# PCB-PWR-DIST.net
KiCad netlist of a schematic drawn in EAGLE
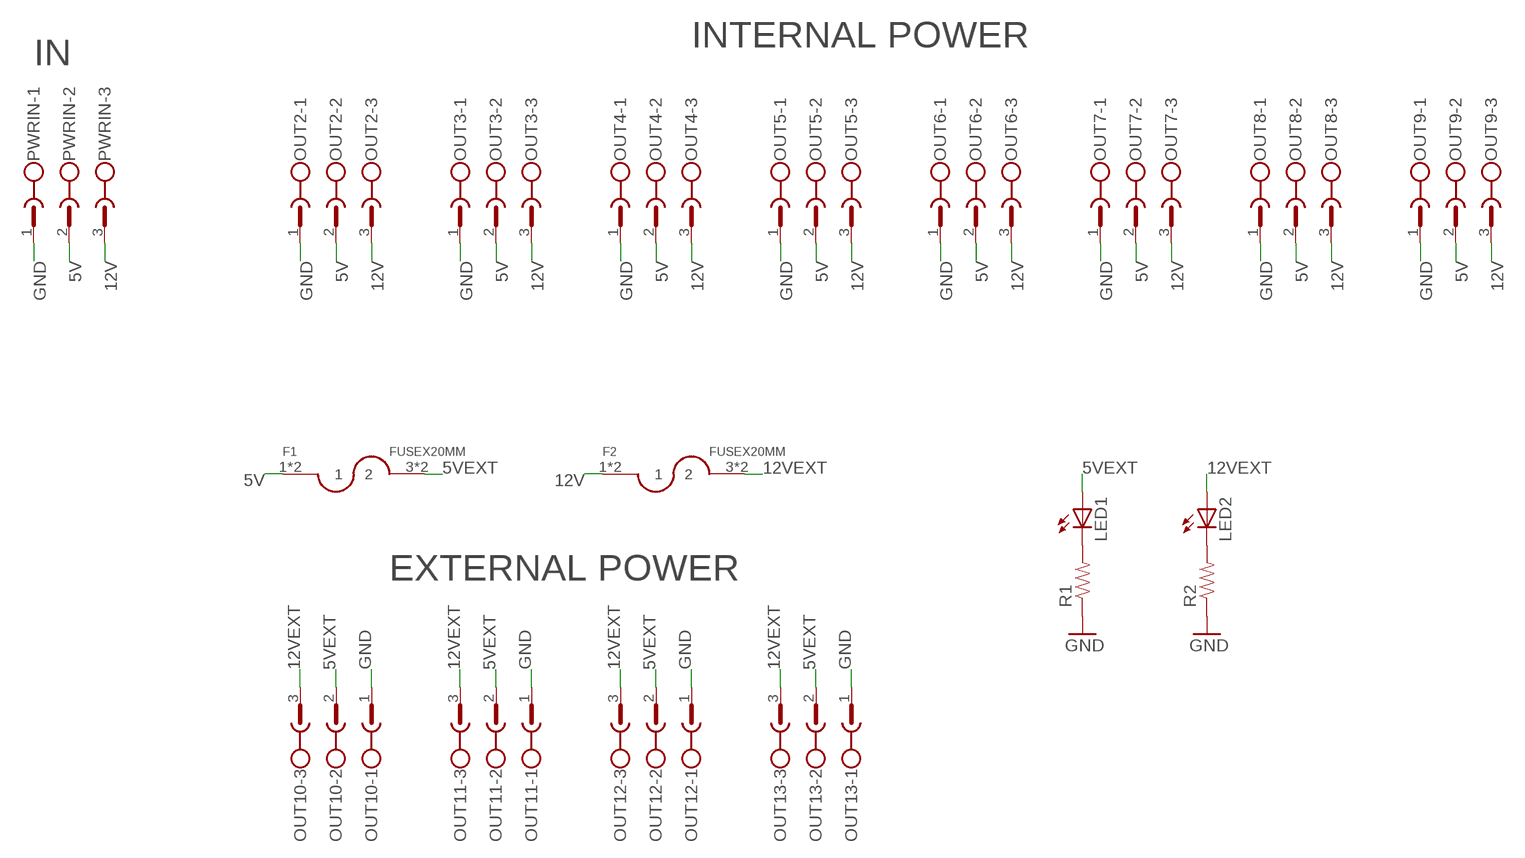
[diagram p0: schematic, sheet 1]

(export (version "E")
  (design (tool "Eeschema 10.0.6"))
  (components
    (comp (ref "F1")
      (value "FUSEX20MM")
      (footprint "eagle-import:FUSE_5MM")
      (libsource (lib "eagle-import") (part "FUSEX20MM"))
    )
    (comp (ref "F2")
      (value "FUSEX20MM")
      (footprint "eagle-import:FUSE_5MM")
      (libsource (lib "eagle-import") (part "FUSEX20MM"))
    )
    (comp (ref "LED1")
      (value "LED3MM")
      (footprint "eagle-import:LED3MM")
      (libsource (lib "eagle-import") (part "LED3MM"))
    )
    (comp (ref "LED2")
      (value "LED3MM")
      (footprint "eagle-import:LED3MM")
      (libsource (lib "eagle-import") (part "LED3MM"))
    )
    (comp (ref "OUT2")
      (value "CON1")
      (footprint "eagle-import:MSTBV3")
      (fields (field (name "MPN") "MSTBV 2,5/3-GF-5.08"))
      (libsource (lib "eagle-import") (part "MSTBV3"))
    )
    (comp (ref "OUT3")
      (value "CON1")
      (footprint "eagle-import:MSTBV3")
      (fields (field (name "MPN") "MSTBV 2,5/3-GF-5.08"))
      (libsource (lib "eagle-import") (part "MSTBV3"))
    )
    (comp (ref "OUT4")
      (value "CON1")
      (footprint "eagle-import:MSTBV3")
      (fields (field (name "MPN") "MSTBV 2,5/3-GF-5.08"))
      (libsource (lib "eagle-import") (part "MSTBV3"))
    )
    (comp (ref "OUT5")
      (value "CON1")
      (footprint "eagle-import:MSTBV3")
      (fields (field (name "MPN") "MSTBV 2,5/3-GF-5.08"))
      (libsource (lib "eagle-import") (part "MSTBV3"))
    )
    (comp (ref "OUT6")
      (value "CON1")
      (footprint "eagle-import:MSTBV3")
      (fields (field (name "MPN") "MSTBV 2,5/3-GF-5.08"))
      (libsource (lib "eagle-import") (part "MSTBV3"))
    )
    (comp (ref "OUT7")
      (value "CON1")
      (footprint "eagle-import:MSTBV3")
      (fields (field (name "MPN") "MSTBV 2,5/3-GF-5.08"))
      (libsource (lib "eagle-import") (part "MSTBV3"))
    )
    (comp (ref "OUT8")
      (value "CON1")
      (footprint "eagle-import:MSTBV3")
      (fields (field (name "MPN") "MSTBV 2,5/3-GF-5.08"))
      (libsource (lib "eagle-import") (part "MSTBV3"))
    )
    (comp (ref "OUT9")
      (value "CON1")
      (footprint "eagle-import:MSTBV3")
      (fields (field (name "MPN") "MSTBV 2,5/3-GF-5.08"))
      (libsource (lib "eagle-import") (part "MSTBV3"))
    )
    (comp (ref "OUT10")
      (value "CON1")
      (footprint "eagle-import:MSTBV3")
      (fields (field (name "MPN") "MSTBV 2,5/3-GF-5.08"))
      (libsource (lib "eagle-import") (part "MSTBV3"))
    )
    (comp (ref "OUT11")
      (value "CON1")
      (footprint "eagle-import:MSTBV3")
      (fields (field (name "MPN") "MSTBV 2,5/3-GF-5.08"))
      (libsource (lib "eagle-import") (part "MSTBV3"))
    )
    (comp (ref "OUT12")
      (value "CON1")
      (footprint "eagle-import:MSTBV3")
      (fields (field (name "MPN") "MSTBV 2,5/3-GF-5.08"))
      (libsource (lib "eagle-import") (part "MSTBV3"))
    )
    (comp (ref "OUT13")
      (value "CON1")
      (footprint "eagle-import:MSTBV3")
      (fields (field (name "MPN") "MSTBV 2,5/3-GF-5.08"))
      (libsource (lib "eagle-import") (part "MSTBV3"))
    )
    (comp (ref "PWRIN")
      (value "CON1")
      (footprint "eagle-import:MSTBV3")
      (fields (field (name "MPN") "MSTBV 2,5/3-GF-5.08"))
      (libsource (lib "eagle-import") (part "MSTBV3"))
    )
    (comp (ref "R1")
      (value "RESISTORPTH-1/4W")
      (footprint "eagle-import:AXIAL-0.4")
      (libsource (lib "eagle-import") (part "RESISTORPTH-1/4W"))
    )
    (comp (ref "R2")
      (value "RESISTORPTH-1/4W")
      (footprint "eagle-import:AXIAL-0.4")
      (libsource (lib "eagle-import") (part "RESISTORPTH-1/4W"))
    )
  )
  (nets
    (net (code "1") (name "/5V") (class "Default")
      (node (ref "F1") (pin "1") (pinfunction "1_1") (pintype "bidirectional"))
      (node (ref "F1") (pin "2") (pinfunction "1_2") (pintype "bidirectional"))
      (node (ref "OUT2") (pin "2") (pinfunction "1_2") (pintype "passive"))
      (node (ref "OUT3") (pin "2") (pinfunction "1_2") (pintype "passive"))
      (node (ref "OUT4") (pin "2") (pinfunction "1_2") (pintype "passive"))
      (node (ref "OUT5") (pin "2") (pinfunction "1_2") (pintype "passive"))
      (node (ref "OUT6") (pin "2") (pinfunction "1_2") (pintype "passive"))
      (node (ref "OUT7") (pin "2") (pinfunction "1_2") (pintype "passive"))
      (node (ref "OUT8") (pin "2") (pinfunction "1_2") (pintype "passive"))
      (node (ref "OUT9") (pin "2") (pinfunction "1_2") (pintype "passive"))
      (node (ref "PWRIN") (pin "2") (pinfunction "1_2") (pintype "passive"))
    )
    (net (code "2") (name "/5VEXT") (class "Default")
      (node (ref "F1") (pin "3") (pinfunction "2_3") (pintype "bidirectional"))
      (node (ref "F1") (pin "4") (pinfunction "2_4") (pintype "bidirectional"))
      (node (ref "LED1") (pin "A") (pinfunction "A_A") (pintype "passive"))
      (node (ref "OUT10") (pin "2") (pinfunction "1_2") (pintype "passive"))
      (node (ref "OUT11") (pin "2") (pinfunction "1_2") (pintype "passive"))
      (node (ref "OUT12") (pin "2") (pinfunction "1_2") (pintype "passive"))
      (node (ref "OUT13") (pin "2") (pinfunction "1_2") (pintype "passive"))
    )
    (net (code "3") (name "/12V") (class "Default")
      (node (ref "F2") (pin "1") (pinfunction "1_1") (pintype "bidirectional"))
      (node (ref "F2") (pin "2") (pinfunction "1_2") (pintype "bidirectional"))
      (node (ref "OUT2") (pin "3") (pinfunction "1_3") (pintype "passive"))
      (node (ref "OUT3") (pin "3") (pinfunction "1_3") (pintype "passive"))
      (node (ref "OUT4") (pin "3") (pinfunction "1_3") (pintype "passive"))
      (node (ref "OUT5") (pin "3") (pinfunction "1_3") (pintype "passive"))
      (node (ref "OUT6") (pin "3") (pinfunction "1_3") (pintype "passive"))
      (node (ref "OUT7") (pin "3") (pinfunction "1_3") (pintype "passive"))
      (node (ref "OUT8") (pin "3") (pinfunction "1_3") (pintype "passive"))
      (node (ref "OUT9") (pin "3") (pinfunction "1_3") (pintype "passive"))
      (node (ref "PWRIN") (pin "3") (pinfunction "1_3") (pintype "passive"))
    )
    (net (code "4") (name "/12VEXT") (class "Default")
      (node (ref "F2") (pin "3") (pinfunction "2_3") (pintype "bidirectional"))
      (node (ref "F2") (pin "4") (pinfunction "2_4") (pintype "bidirectional"))
      (node (ref "LED2") (pin "A") (pinfunction "A_A") (pintype "passive"))
      (node (ref "OUT10") (pin "3") (pinfunction "1_3") (pintype "passive"))
      (node (ref "OUT11") (pin "3") (pinfunction "1_3") (pintype "passive"))
      (node (ref "OUT12") (pin "3") (pinfunction "1_3") (pintype "passive"))
      (node (ref "OUT13") (pin "3") (pinfunction "1_3") (pintype "passive"))
    )
    (net (code "5") (name "GND") (class "Default")
      (node (ref "OUT10") (pin "1") (pinfunction "1_1") (pintype "passive"))
      (node (ref "OUT11") (pin "1") (pinfunction "1_1") (pintype "passive"))
      (node (ref "OUT12") (pin "1") (pinfunction "1_1") (pintype "passive"))
      (node (ref "OUT13") (pin "1") (pinfunction "1_1") (pintype "passive"))
      (node (ref "OUT2") (pin "1") (pinfunction "1_1") (pintype "passive"))
      (node (ref "OUT3") (pin "1") (pinfunction "1_1") (pintype "passive"))
      (node (ref "OUT4") (pin "1") (pinfunction "1_1") (pintype "passive"))
      (node (ref "OUT5") (pin "1") (pinfunction "1_1") (pintype "passive"))
      (node (ref "OUT6") (pin "1") (pinfunction "1_1") (pintype "passive"))
      (node (ref "OUT7") (pin "1") (pinfunction "1_1") (pintype "passive"))
      (node (ref "OUT8") (pin "1") (pinfunction "1_1") (pintype "passive"))
      (node (ref "OUT9") (pin "1") (pinfunction "1_1") (pintype "passive"))
      (node (ref "PWRIN") (pin "1") (pinfunction "1_1") (pintype "passive"))
      (node (ref "R1") (pin "P$1") (pinfunction "1_P$1") (pintype "passive"))
      (node (ref "R2") (pin "P$1") (pinfunction "1_P$1") (pintype "passive"))
    )
    (net (code "6") (name "Net-(LED1-C)") (class "Default")
      (node (ref "LED1") (pin "K") (pinfunction "C_K") (pintype "passive"))
      (node (ref "R1") (pin "P$2") (pinfunction "2_P$2") (pintype "passive"))
    )
    (net (code "7") (name "Net-(LED2-C)") (class "Default")
      (node (ref "LED2") (pin "K") (pinfunction "C_K") (pintype "passive"))
      (node (ref "R2") (pin "P$2") (pinfunction "2_P$2") (pintype "passive"))
    )
  )
)
